# VDC.net
KiCad netlist of a schematic drawn in EAGLE
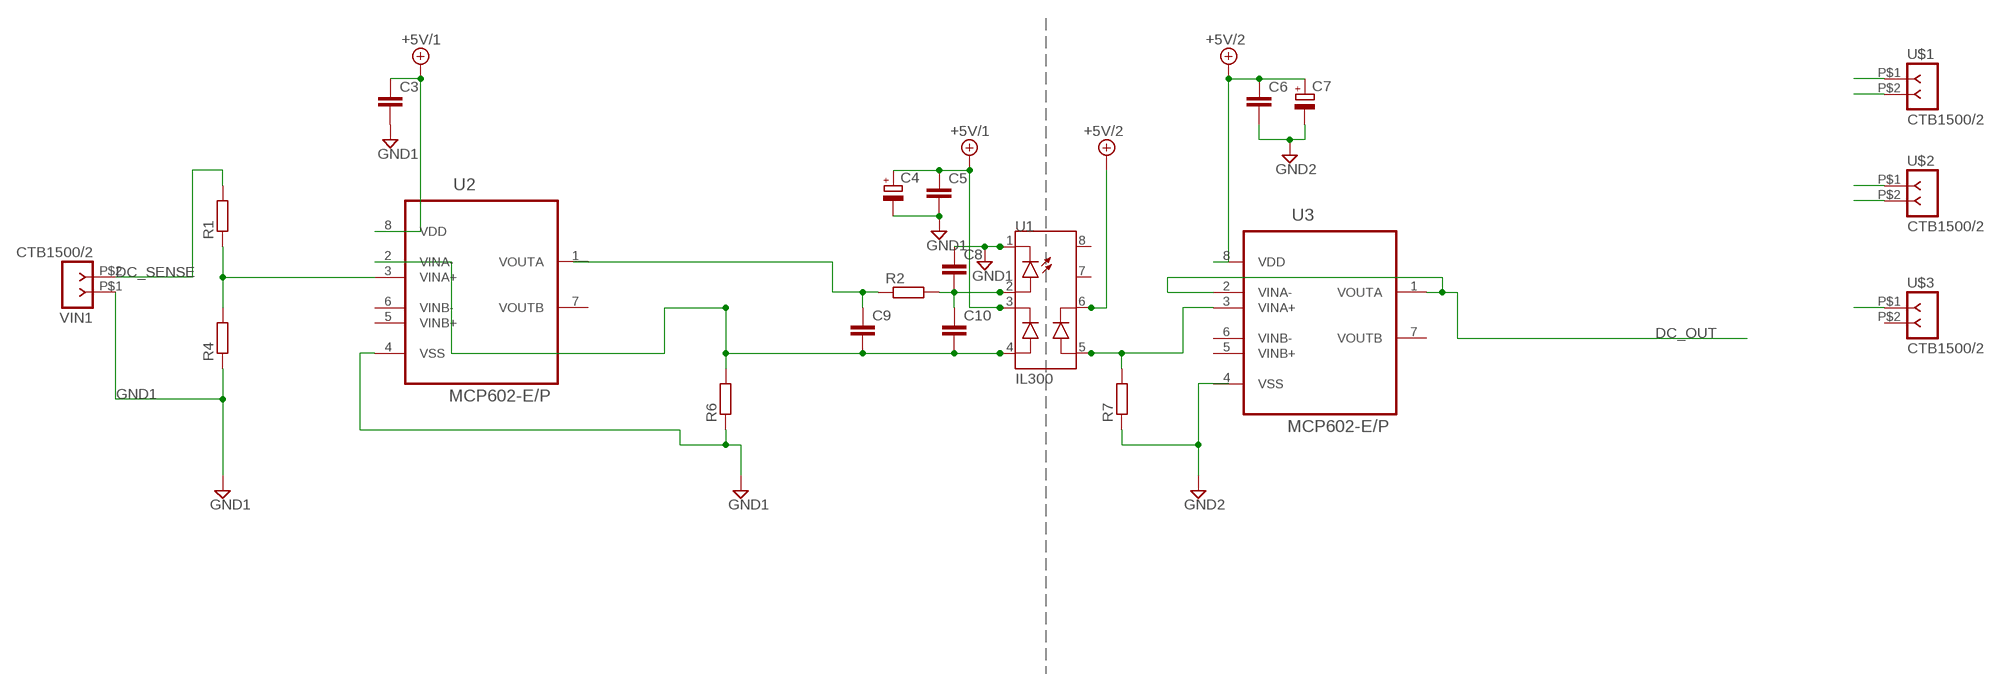
[diagram p0: schematic, sheet 1]

(export (version "E")
  (design (tool "Eeschema 10.0.6"))
  (components
    (comp (ref "C3")
      (value "C-EU025-040X050")
      (footprint "eagle-import:C025-040X050")
      (libsource (lib "eagle-import") (part "C-EU025-040X050"))
    )
    (comp (ref "C4")
      (value "CPOL-EUE2-5")
      (footprint "eagle-import:E2-5")
      (libsource (lib "eagle-import") (part "CPOL-EUE2-5"))
    )
    (comp (ref "C5")
      (value "C-EU025-040X050")
      (footprint "eagle-import:C025-040X050")
      (libsource (lib "eagle-import") (part "C-EU025-040X050"))
    )
    (comp (ref "C6")
      (value "C-EU025-040X050")
      (footprint "eagle-import:C025-040X050")
      (libsource (lib "eagle-import") (part "C-EU025-040X050"))
    )
    (comp (ref "C7")
      (value "CPOL-EUE2-5")
      (footprint "eagle-import:E2-5")
      (libsource (lib "eagle-import") (part "CPOL-EUE2-5"))
    )
    (comp (ref "C8")
      (value "C-EU025-040X050")
      (footprint "eagle-import:C025-040X050")
      (libsource (lib "eagle-import") (part "C-EU025-040X050"))
    )
    (comp (ref "C9")
      (value "C-EU025-040X050")
      (footprint "eagle-import:C025-040X050")
      (libsource (lib "eagle-import") (part "C-EU025-040X050"))
    )
    (comp (ref "C10")
      (value "C-EU025-040X050")
      (footprint "eagle-import:C025-040X050")
      (libsource (lib "eagle-import") (part "C-EU025-040X050"))
    )
    (comp (ref "R1")
      (value "R-EU_0207/10")
      (footprint "eagle-import:0207_10")
      (libsource (lib "eagle-import") (part "R-EU_0207/10"))
    )
    (comp (ref "R2")
      (value "R-EU_0207/10")
      (footprint "eagle-import:0207_10")
      (libsource (lib "eagle-import") (part "R-EU_0207/10"))
    )
    (comp (ref "R4")
      (value "R-EU_0207/10")
      (footprint "eagle-import:0207_10")
      (libsource (lib "eagle-import") (part "R-EU_0207/10"))
    )
    (comp (ref "R6")
      (value "R-EU_0207/10")
      (footprint "eagle-import:0207_10")
      (libsource (lib "eagle-import") (part "R-EU_0207/10"))
    )
    (comp (ref "R7")
      (value "R-EU_0207/10")
      (footprint "eagle-import:0207_10")
      (libsource (lib "eagle-import") (part "R-EU_0207/10"))
    )
    (comp (ref "U$1")
      (value "CTB1500/2")
      (footprint "eagle-import:CTB1500-2")
      (libsource (lib "eagle-import") (part "CTB1500/2"))
    )
    (comp (ref "U$2")
      (value "CTB1500/2")
      (footprint "eagle-import:CTB1500-2")
      (libsource (lib "eagle-import") (part "CTB1500/2"))
    )
    (comp (ref "U$3")
      (value "CTB1500/2")
      (footprint "eagle-import:CTB1500-2")
      (libsource (lib "eagle-import") (part "CTB1500/2"))
    )
    (comp (ref "U1")
      (value "IL300")
      (footprint "eagle-import:DIL08")
      (libsource (lib "eagle-import") (part "IL300"))
    )
    (comp (ref "U2")
      (value "MCP602-E/P")
      (footprint "eagle-import:DIP254P762X508-8P")
      (libsource (lib "eagle-import") (part "MCP602-E/P"))
    )
    (comp (ref "U3")
      (value "MCP602-E/P")
      (footprint "eagle-import:DIP254P762X508-8P")
      (libsource (lib "eagle-import") (part "MCP602-E/P"))
    )
    (comp (ref "VIN1")
      (value "CTB1500/2")
      (footprint "eagle-import:CTB1500-2")
      (libsource (lib "eagle-import") (part "CTB1500/2"))
    )
  )
  (nets
    (net (code "1") (name "+5V{slash}1") (class "Default")
      (node (ref "C3") (pin "1") (pinfunction "1_1") (pintype "passive"))
      (node (ref "C4") (pin "+") (pinfunction "+_+") (pintype "passive"))
      (node (ref "C5") (pin "1") (pinfunction "1_1") (pintype "passive"))
      (node (ref "U$1") (pin "P$2") (pinfunction "2_P$2") (pintype "passive"))
      (node (ref "U1") (pin "3") (pinfunction "C_FB_3") (pintype "passive"))
      (node (ref "U2") (pin "8") (pinfunction "VDD_8") (pintype "power_in"))
    )
    (net (code "2") (name "+5V{slash}2") (class "Default")
      (node (ref "C6") (pin "1") (pinfunction "1_1") (pintype "passive"))
      (node (ref "C7") (pin "+") (pinfunction "+_+") (pintype "passive"))
      (node (ref "U$2") (pin "P$2") (pinfunction "2_P$2") (pintype "passive"))
      (node (ref "U1") (pin "6") (pinfunction "C_OUT_6") (pintype "passive"))
      (node (ref "U3") (pin "8") (pinfunction "VDD_8") (pintype "power_in"))
    )
    (net (code "3") (name "/DC_OUT") (class "Default")
      (node (ref "U$3") (pin "P$1") (pinfunction "1_P$1") (pintype "passive"))
      (node (ref "U3") (pin "1") (pinfunction "VOUTA_1") (pintype "output"))
      (node (ref "U3") (pin "2") (pinfunction "VINA-_2") (pintype "input"))
    )
    (net (code "4") (name "/DC_SENSE") (class "Default")
      (node (ref "R1") (pin "2") (pinfunction "2_2") (pintype "passive"))
      (node (ref "VIN1") (pin "P$2") (pinfunction "2_P$2") (pintype "passive"))
    )
    (net (code "5") (name "/VSS") (class "Default")
      (node (ref "U3") (pin "4") (pinfunction "VSS_4") (pintype "power_in"))
    )
    (net (code "6") (name "GND1") (class "Default")
      (node (ref "C3") (pin "2") (pinfunction "2_2") (pintype "passive"))
      (node (ref "C4") (pin "-") (pinfunction "-_-") (pintype "passive"))
      (node (ref "C5") (pin "2") (pinfunction "2_2") (pintype "passive"))
      (node (ref "C8") (pin "1") (pinfunction "1_1") (pintype "passive"))
      (node (ref "R4") (pin "1") (pinfunction "1_1") (pintype "passive"))
      (node (ref "R6") (pin "1") (pinfunction "1_1") (pintype "passive"))
      (node (ref "U$1") (pin "P$1") (pinfunction "1_P$1") (pintype "passive"))
      (node (ref "U1") (pin "1") (pinfunction "C_LED_1") (pintype "passive"))
      (node (ref "U2") (pin "4") (pinfunction "VSS_4") (pintype "power_in"))
      (node (ref "VIN1") (pin "P$1") (pinfunction "1_P$1") (pintype "passive"))
    )
    (net (code "7") (name "GND2") (class "Default")
      (node (ref "C6") (pin "2") (pinfunction "2_2") (pintype "passive"))
      (node (ref "C7") (pin "-") (pinfunction "-_-") (pintype "passive"))
      (node (ref "R7") (pin "1") (pinfunction "1_1") (pintype "passive"))
      (node (ref "U$2") (pin "P$1") (pinfunction "1_P$1") (pintype "passive"))
    )
    (net (code "8") (name "Net-(C9-Pad1)") (class "Default")
      (node (ref "C9") (pin "1") (pinfunction "1_1") (pintype "passive"))
      (node (ref "R2") (pin "1") (pinfunction "1_1") (pintype "passive"))
    )
    (net (code "9") (name "Net-(U1-A_FB)") (class "Default")
      (node (ref "C10") (pin "2") (pinfunction "2_2") (pintype "passive"))
      (node (ref "C9") (pin "2") (pinfunction "2_2") (pintype "passive"))
      (node (ref "R6") (pin "2") (pinfunction "2_2") (pintype "passive"))
      (node (ref "U1") (pin "4") (pinfunction "A_FB_4") (pintype "passive"))
      (node (ref "U2") (pin "2") (pinfunction "VINA-_2") (pintype "input"))
    )
    (net (code "10") (name "Net-(U1-A_LED)") (class "Default")
      (node (ref "C10") (pin "1") (pinfunction "1_1") (pintype "passive"))
      (node (ref "C8") (pin "2") (pinfunction "2_2") (pintype "passive"))
      (node (ref "R2") (pin "2") (pinfunction "2_2") (pintype "passive"))
      (node (ref "U1") (pin "2") (pinfunction "A_LED_2") (pintype "passive"))
    )
    (net (code "11") (name "Net-(U1-A_OUT)") (class "Default")
      (node (ref "R7") (pin "2") (pinfunction "2_2") (pintype "passive"))
      (node (ref "U1") (pin "5") (pinfunction "A_OUT_5") (pintype "passive"))
      (node (ref "U3") (pin "3") (pinfunction "VINA+_3") (pintype "input"))
    )
    (net (code "12") (name "Net-(U2-VINA+)") (class "Default")
      (node (ref "R1") (pin "1") (pinfunction "1_1") (pintype "passive"))
      (node (ref "R4") (pin "2") (pinfunction "2_2") (pintype "passive"))
      (node (ref "U2") (pin "3") (pinfunction "VINA+_3") (pintype "input"))
    )
    (net (code "13") (name "unconnected-(U$3-2-PadP$2)") (class "Default")
      (node (ref "U$3") (pin "P$2") (pinfunction "2_P$2") (pintype "passive"))
    )
    (net (code "14") (name "unconnected-(U1-PIN7-Pad7)") (class "Default")
      (node (ref "U1") (pin "7") (pinfunction "PIN7_7") (pintype "no_connect"))
    )
    (net (code "15") (name "unconnected-(U1-PIN8-Pad8)") (class "Default")
      (node (ref "U1") (pin "8") (pinfunction "PIN8_8") (pintype "no_connect"))
    )
    (net (code "16") (name "unconnected-(U2-VINB+-Pad5)") (class "Default")
      (node (ref "U2") (pin "5") (pinfunction "VINB+_5") (pintype "input"))
    )
    (net (code "17") (name "unconnected-(U2-VINB--Pad6)") (class "Default")
      (node (ref "U2") (pin "6") (pinfunction "VINB-_6") (pintype "input"))
    )
    (net (code "18") (name "unconnected-(U2-VOUTA-Pad1)") (class "Default")
      (node (ref "U2") (pin "1") (pinfunction "VOUTA_1") (pintype "output"))
    )
    (net (code "19") (name "unconnected-(U2-VOUTB-Pad7)") (class "Default")
      (node (ref "U2") (pin "7") (pinfunction "VOUTB_7") (pintype "output"))
    )
    (net (code "20") (name "unconnected-(U3-VINB+-Pad5)") (class "Default")
      (node (ref "U3") (pin "5") (pinfunction "VINB+_5") (pintype "input"))
    )
    (net (code "21") (name "unconnected-(U3-VINB--Pad6)") (class "Default")
      (node (ref "U3") (pin "6") (pinfunction "VINB-_6") (pintype "input"))
    )
    (net (code "22") (name "unconnected-(U3-VOUTB-Pad7)") (class "Default")
      (node (ref "U3") (pin "7") (pinfunction "VOUTB_7") (pintype "output"))
    )
  )
)
